# motor_driver_schematic.net
KiCad netlist of a schematic drawn in Altium Designer
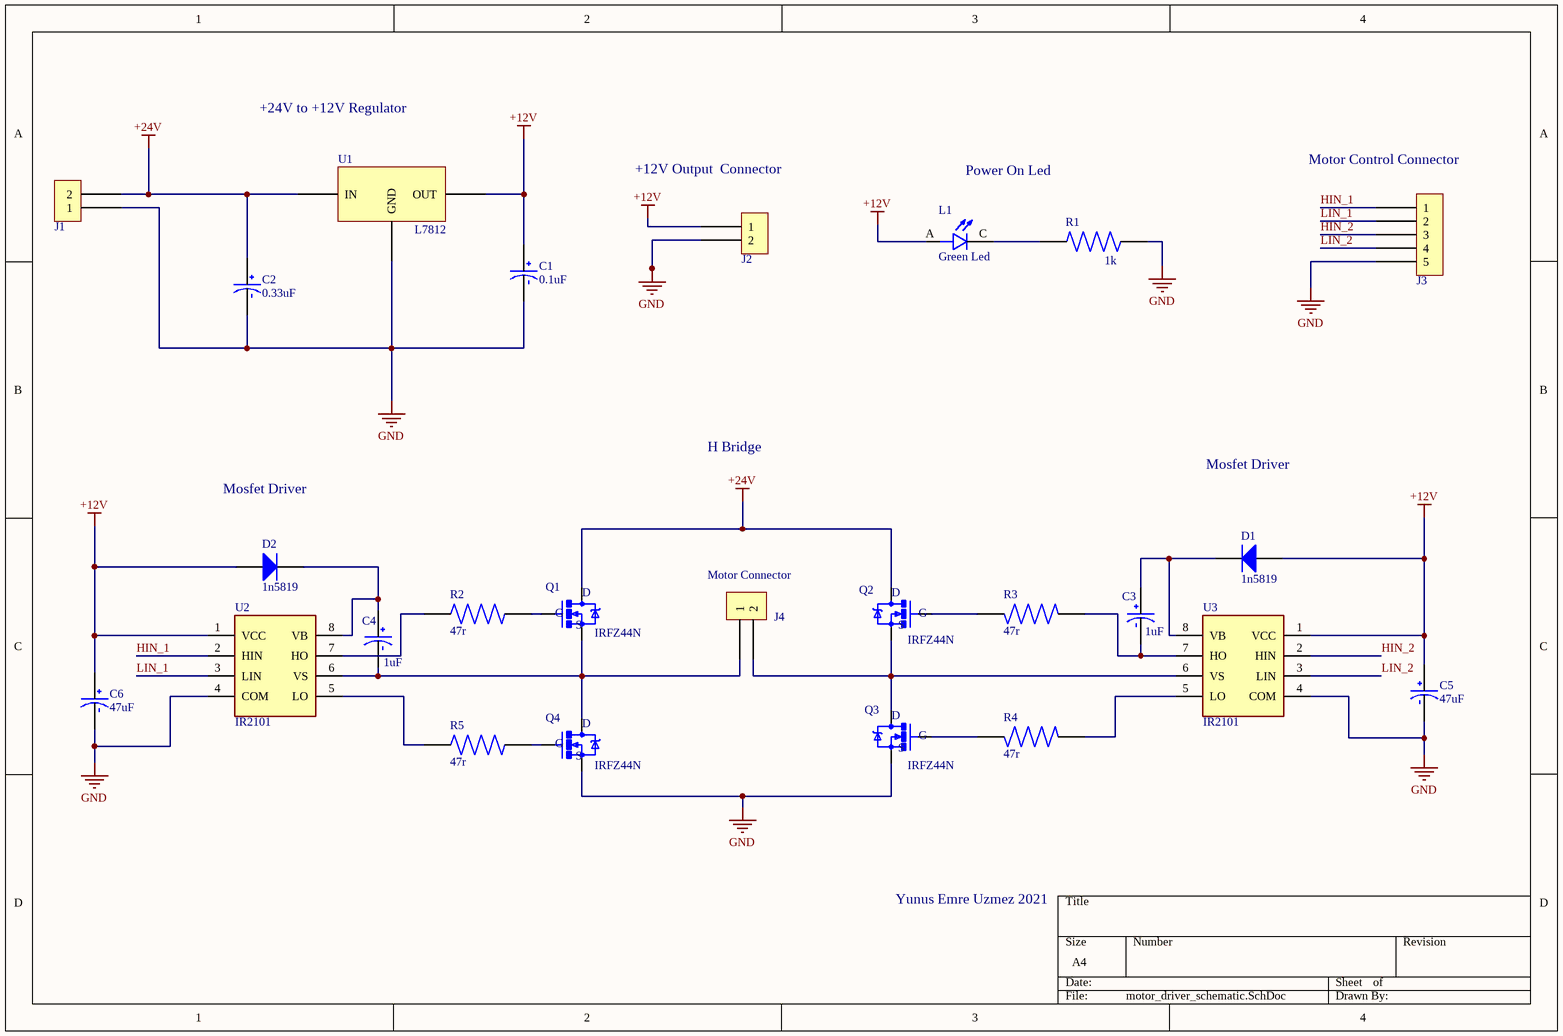
[diagram p0: motor_driver_schematic.SchDoc]

(export (version "E")
  (design (tool "Eeschema 10.0.6"))
  (components
    (comp (ref "C1")
      (value "0.1uF")
      (footprint "Radial Capacitor")
      (description "Aluminium Electrolytic Capacitor Radial Leaded  0.1uF 50V")
      (fields (field (name "Comment") "Cap 0.1uF"))
      (libsource (lib "motor_driver_schLib") (part "Cap 0.1uF"))
    )
    (comp (ref "C2")
      (value "0.33uF")
      (footprint "Radial Capacitor")
      (description "Aluminium Electrolytic Capacitor Radial Leaded  0.33uF 50V")
      (fields (field (name "Comment") "Cap 0.33uF"))
      (libsource (lib "motor_driver_schLib") (part "Cap 0.33uF"))
    )
    (comp (ref "C3")
      (value "1uF")
      (footprint "Radial Capacitor")
      (description "Aluminium Electrolytic Capacitor Radial Leaded  1uF 50V")
      (fields (field (name "Comment") "Cap 1uF"))
      (libsource (lib "motor_driver_schLib") (part "Cap 1uF"))
    )
    (comp (ref "C4")
      (value "1uF")
      (footprint "Radial Capacitor")
      (description "Aluminium Electrolytic Capacitor Radial Leaded  1uF 50V")
      (fields (field (name "Comment") "Cap 1uF"))
      (libsource (lib "") (part "Cap 1uF_1"))
    )
    (comp (ref "C5")
      (value "47uF")
      (footprint "Radial Capacitor")
      (description "Aluminium Electrolytic Capacitor Radial Leaded  1uF 50V")
      (fields (field (name "Comment") "Cap 1uF"))
      (libsource (lib "motor_driver_schLib") (part "Cap 1uF"))
    )
    (comp (ref "C6")
      (value "47uF")
      (footprint "Radial Capacitor")
      (description "Aluminium Electrolytic Capacitor Radial Leaded  1uF 50V")
      (fields (field (name "Comment") "Cap 1uF"))
      (libsource (lib "") (part "Cap 1uF_1"))
    )
    (comp (ref "D1")
      (value "1N5819")
      (footprint "1n5819")
      (description "DIODE SCHOTTKY 1A 40V BULK")
      (fields (field (name "NAME") "1n5819"))
      (libsource (lib "motor_driver_schLib") (part "1N5819"))
    )
    (comp (ref "D2")
      (value "1N5819")
      (footprint "1n5819")
      (description "DIODE SCHOTTKY 1A 40V BULK")
      (fields (field (name "NAME") "1n5819"))
      (libsource (lib "motor_driver_schLib") (part "1N5819"))
    )
    (comp (ref "J1")
      (value "Terminal Block 1x2")
      (footprint "TERMINAL BLOCK 1X2 3.5MM")
      (description "Fixed Terminal Block , screw type, 5.08 , horizontal, 2 poles, CUI Blue, slotted screw, PCB mount")
      (libsource (lib "") (part "Terminal Block 1x2_2"))
    )
    (comp (ref "J2")
      (value "Terminal Block 1x2")
      (footprint "TERMINAL BLOCK 1X2 3.5MM")
      (description "Fixed Terminal Block , screw type, 5.08 , horizontal, 2 poles, CUI Blue, slotted screw, PCB mount")
      (libsource (lib "motor_driver_schLib") (part "Terminal Block 1x2"))
    )
    (comp (ref "J3")
      (value "Header 1x5")
      (footprint "HEADER 1X5 3.5MM")
      (description "5 Pin (1x5) 2.54mm Male Pin Header THT")
      (libsource (lib "motor_driver_schLib") (part "Header 1x5"))
    )
    (comp (ref "J4")
      (value "Terminal Block 1x2")
      (footprint "TERMINAL BLOCK 1X2 3.5MM")
      (description "Fixed Terminal Block , screw type, 5.08 , horizontal, 2 poles, CUI Blue, slotted screw, PCB mount")
      (libsource (lib "") (part "Terminal Block 1x2_1"))
    )
    (comp (ref "L1")
      (value "Led Green")
      (footprint "LED 5MM")
      (description "HQG 5mm Led Green - 400-500 mcd")
      (fields (field (name "NAME") "Green Led"))
      (libsource (lib "motor_driver_schLib") (part "Led Green"))
    )
    (comp (ref "Q1")
      (value "IRFZ44N")
      (footprint "TO-220")
      (fields (field (name "NAME") "IRFZ44N"))
      (libsource (lib "motor_driver_schLib") (part "IRFZ44N"))
    )
    (comp (ref "Q2")
      (value "IRFZ44N")
      (footprint "TO-220")
      (fields (field (name "NAME") "IRFZ44N"))
      (libsource (lib "") (part "IRFZ44N_1"))
    )
    (comp (ref "Q3")
      (value "IRFZ44N")
      (footprint "TO-220")
      (fields (field (name "NAME") "IRFZ44N"))
      (libsource (lib "") (part "IRFZ44N_1"))
    )
    (comp (ref "Q4")
      (value "IRFZ44N")
      (footprint "TO-220")
      (fields (field (name "NAME") "IRFZ44N"))
      (libsource (lib "motor_driver_schLib") (part "IRFZ44N"))
    )
    (comp (ref "R1")
      (value "1k")
      (footprint "RESISTOR THT")
      (description "Carbon Film Resistor Through Hole 1k")
      (fields (field (name "Comment") "Res 1k"))
      (libsource (lib "motor_driver_schLib") (part "Res 1k"))
    )
    (comp (ref "R2")
      (value "47r")
      (footprint "RESISTOR THT")
      (description "Carbon Film Resistor Through Hole 47r")
      (fields (field (name "Comment") "Res 47r"))
      (libsource (lib "motor_driver_schLib") (part "Res 47r"))
    )
    (comp (ref "R3")
      (value "47r")
      (footprint "RESISTOR THT")
      (description "Carbon Film Resistor Through Hole 47r")
      (fields (field (name "Comment") "Res 47r"))
      (libsource (lib "motor_driver_schLib") (part "Res 47r"))
    )
    (comp (ref "R4")
      (value "47r")
      (footprint "RESISTOR THT")
      (description "Carbon Film Resistor Through Hole 47r")
      (fields (field (name "Comment") "Res 47r"))
      (libsource (lib "motor_driver_schLib") (part "Res 47r"))
    )
    (comp (ref "R5")
      (value "47r")
      (footprint "RESISTOR THT")
      (description "Carbon Film Resistor Through Hole 47r")
      (fields (field (name "Comment") "Res 47r"))
      (libsource (lib "motor_driver_schLib") (part "Res 47r"))
    )
    (comp (ref "U1")
      (value "L7812")
      (footprint "TO-220")
      (fields (field (name "NAME") "L7812"))
      (libsource (lib "motor_driver_schLib") (part "L7812"))
    )
    (comp (ref "U2")
      (value "IR2101")
      (footprint "PDIP-8")
      (fields (field (name "NAME") "IR2101"))
      (libsource (lib "motor_driver_schLib") (part "IR2101"))
    )
    (comp (ref "U3")
      (value "IR2101")
      (footprint "PDIP-8")
      (fields (field (name "NAME") "IR2101"))
      (libsource (lib "") (part "IR2101_1"))
    )
  )
  (nets
    (net (code "1") (name "+12V") (class "Default")
      (node (ref "C1") (pin "POS") (pinfunction "POS_POS") (pintype "passive"))
      (node (ref "C5") (pin "POS") (pinfunction "POS_POS") (pintype "passive"))
      (node (ref "C6") (pin "POS") (pinfunction "POS_POS") (pintype "passive"))
      (node (ref "D1") (pin "1") (pinfunction "A_1") (pintype "passive"))
      (node (ref "D2") (pin "1") (pinfunction "A_1") (pintype "passive"))
      (node (ref "J2") (pin "1") (pinfunction "1_1") (pintype "passive"))
      (node (ref "L1") (pin "A") (pinfunction "A_A") (pintype "passive"))
      (node (ref "U1") (pin "3") (pinfunction "OUT_3") (pintype "passive"))
      (node (ref "U2") (pin "1") (pinfunction "VCC_1") (pintype "passive"))
      (node (ref "U3") (pin "1") (pinfunction "VCC_1") (pintype "passive"))
    )
    (net (code "2") (name "+24V") (class "Default")
      (node (ref "C2") (pin "POS") (pinfunction "POS_POS") (pintype "passive"))
      (node (ref "J1") (pin "2") (pinfunction "2_2") (pintype "passive"))
      (node (ref "Q1") (pin "2") (pinfunction "D_2") (pintype "passive"))
      (node (ref "Q2") (pin "2") (pinfunction "D_2") (pintype "passive"))
      (node (ref "U1") (pin "1") (pinfunction "IN_1") (pintype "passive"))
    )
    (net (code "3") (name "/HIN_1") (class "Default")
      (node (ref "J3") (pin "1") (pinfunction "1_1") (pintype "passive"))
      (node (ref "U2") (pin "2") (pinfunction "HIN_2") (pintype "passive"))
    )
    (net (code "4") (name "/HIN_2") (class "Default")
      (node (ref "J3") (pin "3") (pinfunction "3_3") (pintype "passive"))
      (node (ref "U3") (pin "2") (pinfunction "HIN_2") (pintype "passive"))
    )
    (net (code "5") (name "/LIN_1") (class "Default")
      (node (ref "J3") (pin "2") (pinfunction "2_2") (pintype "passive"))
      (node (ref "U2") (pin "3") (pinfunction "LIN_3") (pintype "passive"))
    )
    (net (code "6") (name "/LIN_2") (class "Default")
      (node (ref "J3") (pin "4") (pinfunction "4_4") (pintype "passive"))
      (node (ref "U3") (pin "3") (pinfunction "LIN_3") (pintype "passive"))
    )
    (net (code "7") (name "GND") (class "Default")
      (node (ref "C1") (pin "NEG") (pinfunction "NEG_NEG") (pintype "passive"))
      (node (ref "C2") (pin "NEG") (pinfunction "NEG_NEG") (pintype "passive"))
      (node (ref "C5") (pin "NEG") (pinfunction "NEG_NEG") (pintype "passive"))
      (node (ref "C6") (pin "NEG") (pinfunction "NEG_NEG") (pintype "passive"))
      (node (ref "J1") (pin "1") (pinfunction "1_1") (pintype "passive"))
      (node (ref "J2") (pin "2") (pinfunction "2_2") (pintype "passive"))
      (node (ref "J3") (pin "5") (pinfunction "5_5") (pintype "passive"))
      (node (ref "Q3") (pin "3") (pinfunction "S_3") (pintype "passive"))
      (node (ref "Q4") (pin "3") (pinfunction "S_3") (pintype "passive"))
      (node (ref "R1") (pin "2") (pinfunction "2_2") (pintype "passive"))
      (node (ref "U1") (pin "2") (pinfunction "GND_2") (pintype "passive"))
      (node (ref "U2") (pin "4") (pinfunction "COM_4") (pintype "passive"))
      (node (ref "U3") (pin "4") (pinfunction "COM_4") (pintype "passive"))
    )
    (net (code "8") (name "Net-(D1-K)") (class "Default")
      (node (ref "C3") (pin "POS") (pinfunction "POS_POS") (pintype "passive"))
      (node (ref "D1") (pin "2") (pinfunction "K_2") (pintype "passive"))
      (node (ref "U3") (pin "8") (pinfunction "VB_8") (pintype "passive"))
    )
    (net (code "9") (name "Net-(D2-K)") (class "Default")
      (node (ref "C4") (pin "POS") (pinfunction "POS_POS") (pintype "passive"))
      (node (ref "D2") (pin "2") (pinfunction "K_2") (pintype "passive"))
      (node (ref "U2") (pin "8") (pinfunction "VB_8") (pintype "passive"))
    )
    (net (code "10") (name "Net-(L1-PadC)") (class "Default")
      (node (ref "L1") (pin "C") (pinfunction "C_C") (pintype "passive"))
      (node (ref "R1") (pin "1") (pinfunction "1_1") (pintype "passive"))
    )
    (net (code "11") (name "Net-(Q1-G)") (class "Default")
      (node (ref "Q1") (pin "1") (pinfunction "G_1") (pintype "passive"))
      (node (ref "R2") (pin "2") (pinfunction "2_2") (pintype "passive"))
    )
    (net (code "12") (name "Net-(Q1-S)") (class "Default")
      (node (ref "C4") (pin "NEG") (pinfunction "NEG_NEG") (pintype "passive"))
      (node (ref "J4") (pin "1") (pinfunction "1_1") (pintype "passive"))
      (node (ref "Q1") (pin "3") (pinfunction "S_3") (pintype "passive"))
      (node (ref "Q4") (pin "2") (pinfunction "D_2") (pintype "passive"))
      (node (ref "U2") (pin "6") (pinfunction "VS_6") (pintype "passive"))
    )
    (net (code "13") (name "Net-(Q2-G)") (class "Default")
      (node (ref "Q2") (pin "1") (pinfunction "G_1") (pintype "passive"))
      (node (ref "R3") (pin "2") (pinfunction "2_2") (pintype "passive"))
    )
    (net (code "14") (name "Net-(Q2-S)") (class "Default")
      (node (ref "J4") (pin "2") (pinfunction "2_2") (pintype "passive"))
      (node (ref "Q2") (pin "3") (pinfunction "S_3") (pintype "passive"))
      (node (ref "Q3") (pin "2") (pinfunction "D_2") (pintype "passive"))
      (node (ref "U3") (pin "6") (pinfunction "VS_6") (pintype "passive"))
    )
    (net (code "15") (name "Net-(Q3-G)") (class "Default")
      (node (ref "Q3") (pin "1") (pinfunction "G_1") (pintype "passive"))
      (node (ref "R4") (pin "2") (pinfunction "2_2") (pintype "passive"))
    )
    (net (code "16") (name "Net-(Q4-G)") (class "Default")
      (node (ref "Q4") (pin "1") (pinfunction "G_1") (pintype "passive"))
      (node (ref "R5") (pin "2") (pinfunction "2_2") (pintype "passive"))
    )
    (net (code "17") (name "Net-(U2-HO)") (class "Default")
      (node (ref "R2") (pin "1") (pinfunction "1_1") (pintype "passive"))
      (node (ref "U2") (pin "7") (pinfunction "HO_7") (pintype "passive"))
    )
    (net (code "18") (name "Net-(U2-LO)") (class "Default")
      (node (ref "R5") (pin "1") (pinfunction "1_1") (pintype "passive"))
      (node (ref "U2") (pin "5") (pinfunction "LO_5") (pintype "passive"))
    )
    (net (code "19") (name "Net-(U3-HO)") (class "Default")
      (node (ref "C3") (pin "NEG") (pinfunction "NEG_NEG") (pintype "passive"))
      (node (ref "R3") (pin "1") (pinfunction "1_1") (pintype "passive"))
      (node (ref "U3") (pin "7") (pinfunction "HO_7") (pintype "passive"))
    )
    (net (code "20") (name "Net-(U3-LO)") (class "Default")
      (node (ref "R4") (pin "1") (pinfunction "1_1") (pintype "passive"))
      (node (ref "U3") (pin "5") (pinfunction "LO_5") (pintype "passive"))
    )
  )
)
